# DHJSNoiseConsole.net
KiCad netlist of a schematic drawn in EAGLE
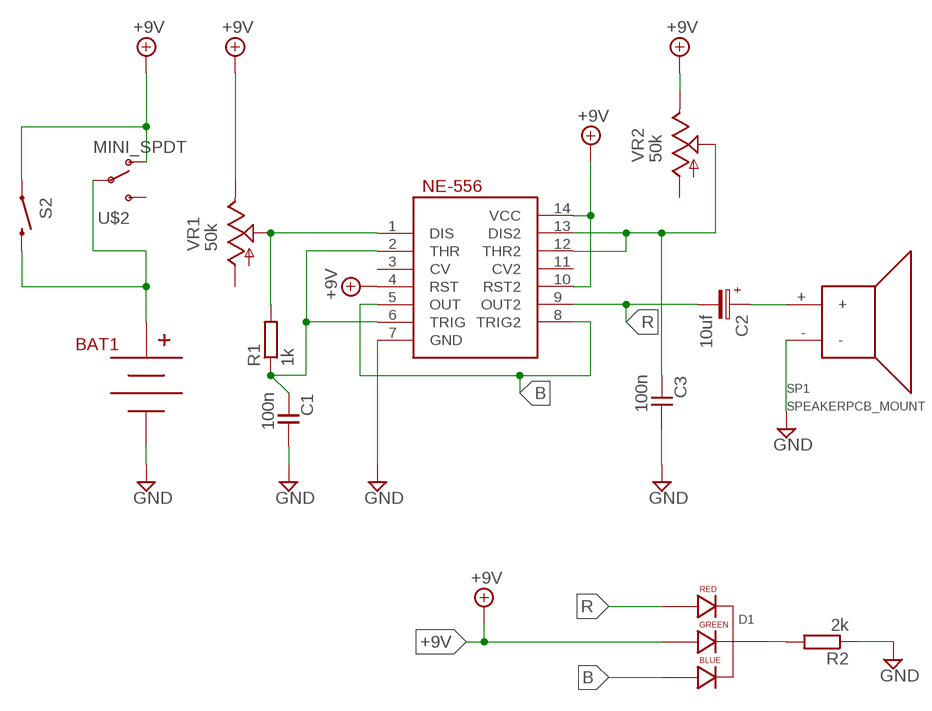
[diagram p0: schematic, sheet 1]

(export (version "E")
  (design (tool "Eeschema 10.0.6"))
  (components
    (comp (ref "BAT1")
      (value "BC9VPC")
      (footprint "eagle-import:BC9VPC")
      (libsource (lib "eagle-import") (part "BC9VPC"))
    )
    (comp (ref "C1")
      (value "100n")
      (footprint "eagle-import:C050-024X044")
      (libsource (lib "eagle-import") (part "C-EU050-024X044"))
    )
    (comp (ref "C2")
      (value "10uf")
      (footprint "eagle-import:050_020")
      (libsource (lib "eagle-import") (part "050-EU"))
    )
    (comp (ref "C3")
      (value "100n")
      (footprint "eagle-import:C050-024X044")
      (libsource (lib "eagle-import") (part "C-EU050-024X044"))
    )
    (comp (ref "D1")
      (value "LED-RGB-CC-THRUCLEAR")
      (footprint "eagle-import:LED-RGB-THRU")
      (libsource (lib "eagle-import") (part "LED-RGB-CC-THRUCLEAR"))
    )
    (comp (ref "NE-556")
      (value "556")
      (footprint "eagle-import:DIL14")
      (libsource (lib "eagle-import") (part "556"))
    )
    (comp (ref "R1")
      (value "1k")
      (footprint "eagle-import:10MM_RESISTOR")
      (libsource (lib "eagle-import") (part "RESISTOR10MM_RESISTOR"))
    )
    (comp (ref "R2")
      (value "2k")
      (footprint "eagle-import:10MM_RESISTOR")
      (libsource (lib "eagle-import") (part "RESISTOR10MM_RESISTOR"))
    )
    (comp (ref "S2")
      (value "SWITCH-MOMENTARY-2SIDE_EZ")
      (footprint "eagle-import:TACTILE-PTH-SIDEEZ")
      (libsource (lib "eagle-import") (part "SWITCH-MOMENTARY-2SIDE_EZ"))
    )
    (comp (ref "SP1")
      (value "SPEAKERPCB_MOUNT")
      (footprint "eagle-import:PCB_MOUNT_SPEAKER")
      (fields (field (name "MFG") "SANCO"))
      (libsource (lib "eagle-import") (part "SPEAKERPCB_MOUNT"))
    )
    (comp (ref "U$2")
      (value "MINI_SPDT")
      (footprint "eagle-import:MINI_SPDT_RIGHTANGLE")
      (libsource (lib "eagle-import") (part "MINI_SPDT"))
    )
    (comp (ref "VR1")
      (value "50k")
      (footprint "eagle-import:9MM_SNAP-IN_POT")
      (libsource (lib "eagle-import") (part "9MM_SNAP-IN_POT_"))
    )
    (comp (ref "VR2")
      (value "50k")
      (footprint "eagle-import:9MM_SNAP-IN_POT")
      (libsource (lib "eagle-import") (part "9MM_SNAP-IN_POT_"))
    )
  )
  (nets
    (net (code "1") (name "+9V") (class "Default")
      (node (ref "D1") (pin "3") (pinfunction "GREEN_CATHODE_3") (pintype "bidirectional"))
      (node (ref "NE-556") (pin "10") (pinfunction "RST2_10") (pintype "bidirectional"))
      (node (ref "NE-556") (pin "14") (pinfunction "VCC_14") (pintype "bidirectional"))
      (node (ref "NE-556") (pin "4") (pinfunction "RST_4") (pintype "bidirectional"))
      (node (ref "S2") (pin "1") (pinfunction "1_1") (pintype "passive"))
      (node (ref "U$2") (pin "UP") (pinfunction "O_UP") (pintype "passive"))
      (node (ref "VR1") (pin "3") (pinfunction "E_3") (pintype "passive"))
      (node (ref "VR2") (pin "3") (pinfunction "E_3") (pintype "passive"))
    )
    (net (code "2") (name "B") (class "Default")
      (node (ref "D1") (pin "4") (pinfunction "BLUE_CATHODE_4") (pintype "bidirectional"))
      (node (ref "NE-556") (pin "5") (pinfunction "OUT_5") (pintype "bidirectional"))
      (node (ref "NE-556") (pin "8") (pinfunction "TRIG2_8") (pintype "bidirectional"))
    )
    (net (code "3") (name "GND") (class "Default")
      (node (ref "BAT1") (pin "V-") (pinfunction "V-_V-") (pintype "bidirectional"))
      (node (ref "C1") (pin "1") (pinfunction "1_1") (pintype "passive"))
      (node (ref "C3") (pin "1") (pinfunction "1_1") (pintype "passive"))
      (node (ref "NE-556") (pin "7") (pinfunction "GND_7") (pintype "bidirectional"))
      (node (ref "R2") (pin "1") (pinfunction "1_1") (pintype "passive"))
      (node (ref "SP1") (pin "-") (pinfunction "-_-") (pintype "bidirectional"))
    )
    (net (code "4") (name "Net-(BAT1-PadV+)") (class "Default")
      (node (ref "BAT1") (pin "V+") (pinfunction "V+_V+") (pintype "bidirectional"))
      (node (ref "S2") (pin "2") (pinfunction "2_2") (pintype "passive"))
      (node (ref "U$2") (pin "COMMON") (pinfunction "COMMON_COMMON") (pintype "passive"))
    )
    (net (code "5") (name "Net-(C2-Pad+)") (class "Default")
      (node (ref "C2") (pin "+") (pinfunction "+_+") (pintype "passive"))
      (node (ref "SP1") (pin "+") (pinfunction "+_+") (pintype "bidirectional"))
    )
    (net (code "6") (name "Net-(D1-CATHODE)") (class "Default")
      (node (ref "D1") (pin "2") (pinfunction "CATHODE_2") (pintype "bidirectional"))
      (node (ref "R2") (pin "2") (pinfunction "2_2") (pintype "passive"))
    )
    (net (code "7") (name "Net-(NE-556-DIS)") (class "Default")
      (node (ref "NE-556") (pin "1") (pinfunction "DIS_1") (pintype "bidirectional"))
      (node (ref "R1") (pin "2") (pinfunction "2_2") (pintype "passive"))
      (node (ref "VR1") (pin "2") (pinfunction "S_2") (pintype "passive"))
    )
    (net (code "8") (name "Net-(NE-556-DIS2)") (class "Default")
      (node (ref "C3") (pin "2") (pinfunction "2_2") (pintype "passive"))
      (node (ref "NE-556") (pin "12") (pinfunction "THR2_12") (pintype "bidirectional"))
      (node (ref "NE-556") (pin "13") (pinfunction "DIS2_13") (pintype "bidirectional"))
      (node (ref "VR2") (pin "2") (pinfunction "S_2") (pintype "passive"))
    )
    (net (code "9") (name "Net-(NE-556-THR)") (class "Default")
      (node (ref "C1") (pin "2") (pinfunction "2_2") (pintype "passive"))
      (node (ref "NE-556") (pin "2") (pinfunction "THR_2") (pintype "bidirectional"))
      (node (ref "NE-556") (pin "6") (pinfunction "TRIG_6") (pintype "bidirectional"))
      (node (ref "R1") (pin "1") (pinfunction "1_1") (pintype "passive"))
    )
    (net (code "10") (name "R") (class "Default")
      (node (ref "C2") (pin "-") (pinfunction "-_-") (pintype "passive"))
      (node (ref "D1") (pin "1") (pinfunction "RED_CATHODE_1") (pintype "bidirectional"))
      (node (ref "NE-556") (pin "9") (pinfunction "OUT2_9") (pintype "bidirectional"))
    )
    (net (code "11") (name "unconnected-(NE-556-CV-Pad3)") (class "Default")
      (node (ref "NE-556") (pin "3") (pinfunction "CV_3") (pintype "bidirectional"))
    )
    (net (code "12") (name "unconnected-(NE-556-CV2-Pad11)") (class "Default")
      (node (ref "NE-556") (pin "11") (pinfunction "CV2_11") (pintype "bidirectional"))
    )
    (net (code "13") (name "unconnected-(U$2-S-PadDOWN)") (class "Default")
      (node (ref "U$2") (pin "DOWN") (pinfunction "S_DOWN") (pintype "passive"))
    )
    (net (code "14") (name "unconnected-(VR1-A-Pad1)") (class "Default")
      (node (ref "VR1") (pin "1") (pinfunction "A_1") (pintype "passive"))
    )
    (net (code "15") (name "unconnected-(VR2-A-Pad1)") (class "Default")
      (node (ref "VR2") (pin "1") (pinfunction "A_1") (pintype "passive"))
    )
  )
)
